# power.net
KiCad netlist of a schematic drawn in Altium Designer
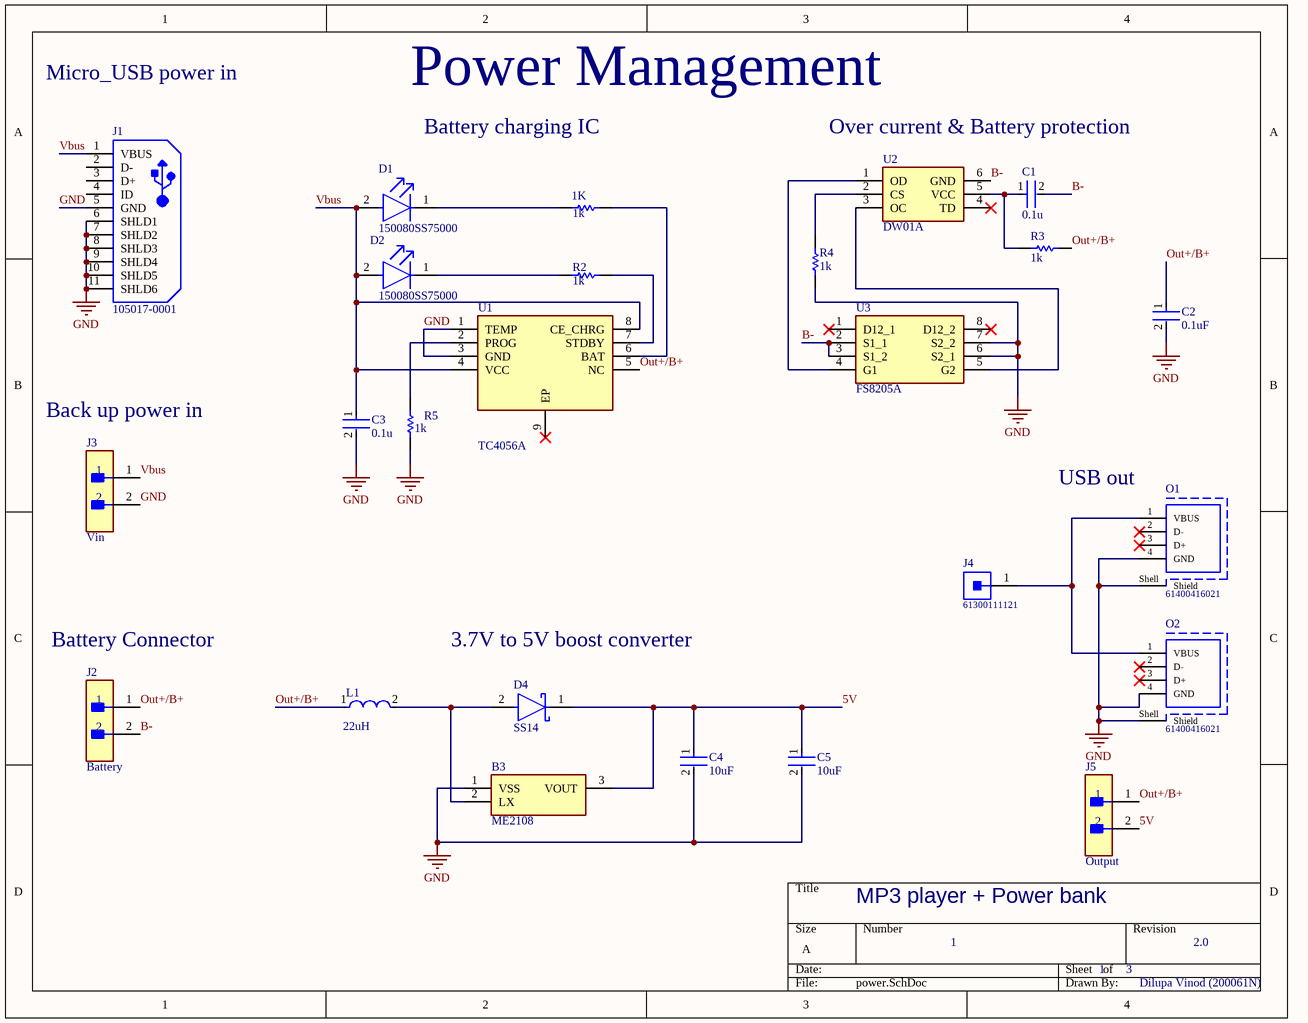
[diagram p0: power.SchDoc]

(export (version "E")
  (design (tool "Eeschema 10.0.6"))
  (components
    (comp (ref "1K")
      (value "1k")
      (footprint "RESC2013X50X30LL20T20")
      (fields (field (name "MANUFACTURER") "Vishay Dale") (field (name "PART NUMBER") "CRCW08050000Z0EA"))
      (libsource (lib "Altium Content Vault") (part "RES"))
    )
    (comp (ref "B3")
      (value "ME2108")
      (footprint "SOT95P250X130-3N")
      (description "6.5V 400mA SOT-23(SOT-23-3) DC-DC Converters RoHS")
      (fields (field (name "MANUFACTURER_PART_NUMBER") "ME2108A33M3G"))
      (libsource (lib "Integrated_Library1") (part "ME2108A33M3G"))
    )
    (comp (ref "C1")
      (value "0.1u")
      (footprint "FP-CL10-IPC_C")
      (description "Cap Ceramic 100nF 16V X7R ±5% Pad SMD 0603 +125°C T/R")
      (fields (field (name "TOLERANCE") "5%"))
      (libsource (lib "Altium Content Vault") (part "b4654b650e69147ec39a6b967a45e02"))
    )
    (comp (ref "C2")
      (value "0.1uF")
      (footprint "FP-C0805C-DN-MFG")
      (description "CAP CER 0.22UF 50V X7R 0805")
      (fields
        (field (name "MANUFACTURER") "KEMET")
        (field (name "OCTOPART") "https://octopart.com/c0805c224k5ractu-kemet-144670")
      )
      (libsource (lib "Altium Content Vault") (part "b4654b650e69147ec39a6b967a45e02"))
    )
    (comp (ref "C3")
      (value "0.1u")
      (footprint "FP-C0805C-DN-MFG")
      (description "CAP CER 0.22UF 50V X7R 0805")
      (fields
        (field (name "MANUFACTURER") "KEMET")
        (field (name "OCTOPART") "https://octopart.com/c0805c224k5ractu-kemet-144670")
      )
      (libsource (lib "Altium Content Vault") (part "b4654b650e69147ec39a6b967a45e02"))
    )
    (comp (ref "C4")
      (value "10uF")
      (footprint "FP-C0805C-DN-MFG")
      (description "CAP CER 0.22UF 50V X7R 0805")
      (fields
        (field (name "MANUFACTURER") "KEMET")
        (field (name "OCTOPART") "https://octopart.com/c0805c224k5ractu-kemet-144670")
      )
      (libsource (lib "Altium Content Vault") (part "b4654b650e69147ec39a6b967a45e02"))
    )
    (comp (ref "C5")
      (value "10uF")
      (footprint "FP-C0805C-DN-MFG")
      (description "CAP CER 0.22UF 50V X7R 0805")
      (fields
        (field (name "MANUFACTURER") "KEMET")
        (field (name "OCTOPART") "https://octopart.com/c0805c224k5ractu-kemet-144670")
      )
      (libsource (lib "Altium Content Vault") (part "b4654b650e69147ec39a6b967a45e02"))
    )
    (comp (ref "D1")
      (value "150080SS75000")
      (footprint "FP-150080SS75000-MFG")
      (description "LED RED CLEAR 0805 SMD")
      (libsource (lib "Altium Content Vault") (part "8706943c75ba83719d021d2fdc84c58"))
    )
    (comp (ref "D2")
      (value "150080SS75000")
      (footprint "FP-150080SS75000-MFG")
      (description "LED RED CLEAR 0805 SMD")
      (libsource (lib "Altium Content Vault") (part "8706943c75ba83719d021d2fdc84c58"))
    )
    (comp (ref "D4")
      (value "SS14")
      (footprint "FP-95400-MFG")
      (description "DIODE SCHOTTKY 40V 1A DO214AC")
      (fields
        (field (name "OCTOPART") "https://octopart.com/ss14-e3%2F61t-vishay-39552847")
        (field (name "MANUFACTURER") "Vishay")
      )
      (libsource (lib "Components - 30.04.23 - 00.58") (part "CMP-02539-000035-1"))
    )
    (comp (ref "J1")
      (value "105017-0001")
      (footprint "USB-MICRO-B_V")
      (fields (field (name "MANUFACTURER") "Molex"))
      (libsource (lib "Altium Content Vault") (part "USB-5-6SHLD"))
    )
    (comp (ref "J2")
      (value "Battery")
      (footprint "FP-M20-9990246-MFG")
      (description "CONN HEADER VERT 2POS 2.54MM")
      (fields
        (field (name "OCTOPART") "https://octopart.com/m20-9990246-harwin-2590635")
        (field (name "MANUFACTURER") "Harwin")
      )
      (libsource (lib "Altium Content Vault") (part "3bc925449376181038e59eaffc5286c"))
    )
    (comp (ref "J3")
      (value "Vin")
      (footprint "FP-M20-9990246-MFG")
      (description "CONN HEADER VERT 2POS 2.54MM")
      (fields
        (field (name "OCTOPART") "https://octopart.com/m20-9990246-harwin-2590635")
        (field (name "MANUFACTURER") "Harwin")
      )
      (libsource (lib "Altium Content Vault") (part "3bc925449376181038e59eaffc5286c"))
    )
    (comp (ref "J4")
      (value "61300111121")
      (footprint "61300111121")
      (description "THT Vertical Pin Header WR-PHD, Pitch 2.54 mm, Single Row, 1 pins")
      (fields
        (field (name "MANUFACTURER") "Wurth Elektronik")
        (field (name "MANUFACTURER_1") "Wurth Electronics")
        (field (name "PUBLISHER") "WurthElektronik")
      )
      (libsource (lib "MP3_Power_bank") (part "CMP-1502-01058-1"))
    )
    (comp (ref "J5")
      (value "Output")
      (footprint "FP-M20-9990246-MFG")
      (description "CONN HEADER VERT 2POS 2.54MM")
      (fields
        (field (name "OCTOPART") "https://octopart.com/m20-9990246-harwin-2590635")
        (field (name "MANUFACTURER") "Harwin")
      )
      (libsource (lib "Altium Content Vault") (part "3bc925449376181038e59eaffc5286c"))
    )
    (comp (ref "L1")
      (value "22uH")
      (footprint "FP-NR6045-MFG")
      (description "Shielded Wirewound Inductor 22uH 20% 1.5A 0.1495Ω SMD")
      (fields (field (name "TOLERANCE") "20%"))
      (libsource (lib "Altium Content Vault") (part "725321dda6339637d4d059423bc1c3c"))
    )
    (comp (ref "O1")
      (value "61400416021")
      (footprint "61400416021")
      (description "USB 2.0 Type A Receptacle WR-COM, Horizontal, THT")
      (fields
        (field (name "MANUFACTURER") "Wurth Elektronik")
        (field (name "MANUFACTURER_1") "Wurth Electronics")
        (field (name "PUBLISHER") "WurthElektronik")
      )
      (libsource (lib "MP3") (part "CMP-1502-03227-1"))
    )
    (comp (ref "O2")
      (value "61400416021")
      (footprint "61400416021")
      (description "USB 2.0 Type A Receptacle WR-COM, Horizontal, THT")
      (fields
        (field (name "MANUFACTURER") "Wurth Elektronik")
        (field (name "MANUFACTURER_1") "Wurth Electronics")
        (field (name "PUBLISHER") "WurthElektronik")
      )
      (libsource (lib "MP3") (part "CMP-1502-03227-1"))
    )
    (comp (ref "R2")
      (value "1k")
      (footprint "RESC2013X50X30LL20T20")
      (fields (field (name "MANUFACTURER") "Vishay Dale") (field (name "PART NUMBER") "CRCW08050000Z0EA"))
      (libsource (lib "Altium Content Vault") (part "RES"))
    )
    (comp (ref "R3")
      (value "1k")
      (footprint "RESC2013X50X30LL20T20")
      (fields (field (name "MANUFACTURER") "Vishay Dale") (field (name "PART NUMBER") "CRCW08050000Z0EA"))
      (libsource (lib "Altium Content Vault") (part "RES"))
    )
    (comp (ref "R4")
      (value "1k")
      (footprint "RESC2013X50X30LL20T20")
      (fields (field (name "MANUFACTURER") "Vishay Dale") (field (name "PART NUMBER") "CRCW08050000Z0EA"))
      (libsource (lib "Altium Content Vault") (part "RES"))
    )
    (comp (ref "R5")
      (value "1k")
      (footprint "RESC2013X50X30LL20T20")
      (fields (field (name "MANUFACTURER") "Vishay Dale") (field (name "PART NUMBER") "CRCW08050000Z0EA"))
      (libsource (lib "Altium Content Vault") (part "RES"))
    )
    (comp (ref "U1")
      (value "TC4056A")
      (footprint "SamacSys:SOIC127P600X175-9N")
      (description "Integrated Circuit")
      (libsource (lib "*") (part "TC4056A"))
    )
    (comp (ref "U2")
      (value "DW01A")
      (footprint "SOT95P280X135-6N")
      (description "Integrated Circuit")
      (fields (field (name "MANUFACTURER_PART_NUMBER") "DW01A-G"))
      (libsource (lib "MP3") (part "DW01A-G"))
    )
    (comp (ref "U3")
      (value "FS8205A")
      (footprint "SOP65P640X120-8N")
      (description "MOSFET (N-Channel)")
      (libsource (lib "MP3") (part "FS8205A"))
    )
  )
  (nets
    (net (code "1") (name "/5V") (class "Default")
      (node (ref "B3") (pin "3") (pinfunction "VOUT_3") (pintype "passive"))
      (node (ref "C4") (pin "1") (pinfunction "1_1") (pintype "passive"))
      (node (ref "C5") (pin "1") (pinfunction "1_1") (pintype "passive"))
      (node (ref "D4") (pin "1") (pinfunction "C_1") (pintype "passive"))
      (node (ref "J5") (pin "2") (pinfunction "2_2") (pintype "passive"))
    )
    (net (code "3") (name "/B-") (class "Default")
      (node (ref "C1") (pin "2") (pinfunction "2_2") (pintype "passive"))
      (node (ref "J2") (pin "2") (pinfunction "2_2") (pintype "passive"))
      (node (ref "U2") (pin "6") (pinfunction "GND_6") (pintype "passive"))
      (node (ref "U3") (pin "2") (pinfunction "S1_1_2") (pintype "passive"))
      (node (ref "U3") (pin "3") (pinfunction "S1_2_3") (pintype "passive"))
    )
    (net (code "4") (name "/Out+{slash}B+") (class "Default")
      (node (ref "C2") (pin "1") (pinfunction "1_1") (pintype "passive"))
      (node (ref "J2") (pin "1") (pinfunction "1_1") (pintype "passive"))
      (node (ref "J5") (pin "1") (pinfunction "1_1") (pintype "passive"))
      (node (ref "L1") (pin "1") (pinfunction "1_1") (pintype "passive"))
      (node (ref "R3") (pin "1") (pinfunction "1_1") (pintype "passive"))
      (node (ref "U1") (pin "5") (pinfunction "NC_5") (pintype "passive"))
    )
    (net (code "5") (name "/Vbus") (class "Default")
      (node (ref "C3") (pin "1") (pinfunction "1_1") (pintype "passive"))
      (node (ref "D1") (pin "2") (pinfunction "A_2") (pintype "passive"))
      (node (ref "D2") (pin "2") (pinfunction "A_2") (pintype "passive"))
      (node (ref "J1") (pin "1") (pinfunction "VBUS_1") (pintype "passive"))
      (node (ref "J3") (pin "1") (pinfunction "1_1") (pintype "passive"))
      (node (ref "U1") (pin "4") (pinfunction "VCC_4") (pintype "passive"))
      (node (ref "U1") (pin "8") (pinfunction "CE_CHRG_8") (pintype "passive"))
    )
    (net (code "6") (name "GND") (class "Default")
      (node (ref "B3") (pin "1") (pinfunction "VSS_1") (pintype "passive"))
      (node (ref "C2") (pin "2") (pinfunction "2_2") (pintype "passive"))
      (node (ref "C3") (pin "2") (pinfunction "2_2") (pintype "passive"))
      (node (ref "C4") (pin "2") (pinfunction "2_2") (pintype "passive"))
      (node (ref "C5") (pin "2") (pinfunction "2_2") (pintype "passive"))
      (node (ref "J1") (pin "10") (pinfunction "SHLD5_10") (pintype "passive"))
      (node (ref "J1") (pin "11") (pinfunction "SHLD6_11") (pintype "passive"))
      (node (ref "J1") (pin "5") (pinfunction "GND_5") (pintype "passive"))
      (node (ref "J1") (pin "6") (pinfunction "SHLD1_6") (pintype "passive"))
      (node (ref "J1") (pin "7") (pinfunction "SHLD2_7") (pintype "passive"))
      (node (ref "J1") (pin "8") (pinfunction "SHLD3_8") (pintype "passive"))
      (node (ref "J1") (pin "9") (pinfunction "SHLD4_9") (pintype "passive"))
      (node (ref "J3") (pin "2") (pinfunction "2_2") (pintype "passive"))
      (node (ref "O1") (pin "4") (pinfunction "GND_4") (pintype "passive"))
      (node (ref "O1") (pin "Shell") (pinfunction "Shield_Shell") (pintype "passive"))
      (node (ref "O2") (pin "4") (pinfunction "GND_4") (pintype "passive"))
      (node (ref "O2") (pin "Shell") (pinfunction "Shield_Shell") (pintype "passive"))
      (node (ref "R4") (pin "1") (pinfunction "1_1") (pintype "passive"))
      (node (ref "R5") (pin "1") (pinfunction "1_1") (pintype "passive"))
      (node (ref "U1") (pin "1") (pinfunction "TEMP_1") (pintype "passive"))
      (node (ref "U1") (pin "3") (pinfunction "GND_3") (pintype "passive"))
      (node (ref "U3") (pin "6") (pinfunction "S2_1_6") (pintype "passive"))
      (node (ref "U3") (pin "7") (pinfunction "S2_2_7") (pintype "passive"))
    )
    (net (code "7") (name "Net-(B3-LX)") (class "Default")
      (node (ref "B3") (pin "2") (pinfunction "LX_2") (pintype "passive"))
      (node (ref "D4") (pin "2") (pinfunction "A_2") (pintype "passive"))
      (node (ref "L1") (pin "2") (pinfunction "2_2") (pintype "passive"))
    )
    (net (code "8") (name "Net-(D1-C)") (class "Default")
      (node (ref "1K") (pin "1") (pinfunction "1_1") (pintype "passive"))
      (node (ref "D1") (pin "1") (pinfunction "C_1") (pintype "passive"))
    )
    (net (code "9") (name "Net-(D2-C)") (class "Default")
      (node (ref "D2") (pin "1") (pinfunction "C_1") (pintype "passive"))
      (node (ref "R2") (pin "1") (pinfunction "1_1") (pintype "passive"))
    )
    (net (code "10") (name "Net-(O1-VBUS)") (class "Default")
      (node (ref "J4") (pin "1") (pinfunction "1_1") (pintype "passive"))
      (node (ref "O1") (pin "1") (pinfunction "VBUS_1") (pintype "passive"))
      (node (ref "O2") (pin "1") (pinfunction "VBUS_1") (pintype "passive"))
    )
    (net (code "11") (name "Net-(U1-BAT)") (class "Default")
      (node (ref "1K") (pin "2") (pinfunction "2_2") (pintype "passive"))
      (node (ref "U1") (pin "6") (pinfunction "BAT_6") (pintype "passive"))
    )
    (net (code "12") (name "Net-(U1-PROG)") (class "Default")
      (node (ref "R5") (pin "2") (pinfunction "2_2") (pintype "passive"))
      (node (ref "U1") (pin "2") (pinfunction "PROG_2") (pintype "passive"))
    )
    (net (code "13") (name "Net-(U1-STDBY)") (class "Default")
      (node (ref "R2") (pin "2") (pinfunction "2_2") (pintype "passive"))
      (node (ref "U1") (pin "7") (pinfunction "STDBY_7") (pintype "passive"))
    )
    (net (code "14") (name "Net-(U2-CS)") (class "Default")
      (node (ref "R4") (pin "2") (pinfunction "2_2") (pintype "passive"))
      (node (ref "U2") (pin "2") (pinfunction "CS_2") (pintype "passive"))
    )
    (net (code "15") (name "Net-(U2-OC)") (class "Default")
      (node (ref "U2") (pin "3") (pinfunction "OC_3") (pintype "passive"))
      (node (ref "U3") (pin "5") (pinfunction "G2_5") (pintype "passive"))
    )
    (net (code "16") (name "Net-(U2-OD)") (class "Default")
      (node (ref "U2") (pin "1") (pinfunction "OD_1") (pintype "passive"))
      (node (ref "U3") (pin "4") (pinfunction "G1_4") (pintype "passive"))
    )
    (net (code "17") (name "Net-(U2-VCC)") (class "Default")
      (node (ref "C1") (pin "1") (pinfunction "1_1") (pintype "passive"))
      (node (ref "R3") (pin "2") (pinfunction "2_2") (pintype "passive"))
      (node (ref "U2") (pin "5") (pinfunction "VCC_5") (pintype "passive"))
    )
    (net (code "18") (name "unconnected-(J1-D+-Pad3)") (class "Default")
      (node (ref "J1") (pin "3") (pinfunction "D+_3") (pintype "passive"))
    )
    (net (code "19") (name "unconnected-(J1-D--Pad2)") (class "Default")
      (node (ref "J1") (pin "2") (pinfunction "D-_2") (pintype "passive"))
    )
    (net (code "20") (name "unconnected-(J1-ID-Pad4)") (class "Default")
      (node (ref "J1") (pin "4") (pinfunction "ID_4") (pintype "passive"))
    )
    (net (code "21") (name "unconnected-(O1-D+-Pad3)") (class "Default")
      (node (ref "O1") (pin "3") (pinfunction "D+_3") (pintype "passive+no_connect"))
    )
    (net (code "22") (name "unconnected-(O1-D--Pad2)") (class "Default")
      (node (ref "O1") (pin "2") (pinfunction "D-_2") (pintype "passive+no_connect"))
    )
    (net (code "23") (name "unconnected-(O2-D+-Pad3)") (class "Default")
      (node (ref "O2") (pin "3") (pinfunction "D+_3") (pintype "passive+no_connect"))
    )
    (net (code "24") (name "unconnected-(O2-D--Pad2)") (class "Default")
      (node (ref "O2") (pin "2") (pinfunction "D-_2") (pintype "passive+no_connect"))
    )
    (net (code "25") (name "unconnected-(U1-EP-Pad9)") (class "Default")
      (node (ref "U1") (pin "9") (pinfunction "EP_9") (pintype "passive+no_connect"))
    )
    (net (code "26") (name "unconnected-(U2-TD-Pad4)") (class "Default")
      (node (ref "U2") (pin "4") (pinfunction "TD_4") (pintype "passive+no_connect"))
    )
    (net (code "27") (name "unconnected-(U3-D12_1-Pad1)") (class "Default")
      (node (ref "U3") (pin "1") (pinfunction "D12_1_1") (pintype "passive+no_connect"))
    )
    (net (code "28") (name "unconnected-(U3-D12_2-Pad8)") (class "Default")
      (node (ref "U3") (pin "8") (pinfunction "D12_2_8") (pintype "passive+no_connect"))
    )
  )
)
